# Verbinder_jr1.net
KiCad netlist of a schematic drawn in EAGLE
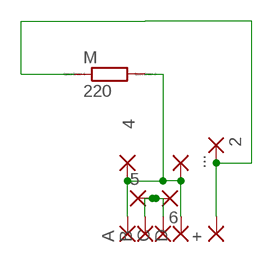
[diagram p0: schematic, sheet 1]

(export (version "E")
  (design (tool "Eeschema 10.0.6"))
  (components
    (comp (ref "+")
      (value "SMD2")
      (footprint "eagle-import:SMD1,27-2,54")
      (libsource (lib "eagle-import") (part "SMD2"))
    )
    (comp (ref "...")
      (value "SMD2")
      (footprint "eagle-import:SMD1,27-2,54")
      (libsource (lib "eagle-import") (part "SMD2"))
    )
    (comp (ref "2")
      (value "SMD2")
      (footprint "eagle-import:SMD1,27-2,54")
      (libsource (lib "eagle-import") (part "SMD2"))
    )
    (comp (ref "4")
      (value "SMD2")
      (footprint "eagle-import:SMD1,27-2,54")
      (libsource (lib "eagle-import") (part "SMD2"))
    )
    (comp (ref "5")
      (value "SMD2")
      (footprint "eagle-import:SMD1,27-2,54")
      (libsource (lib "eagle-import") (part "SMD2"))
    )
    (comp (ref "6")
      (value "SMD2")
      (footprint "eagle-import:SMD1,27-2,54")
      (libsource (lib "eagle-import") (part "SMD2"))
    )
    (comp (ref "A")
      (value "SMD2")
      (footprint "eagle-import:SMD1,27-2,54")
      (libsource (lib "eagle-import") (part "SMD2"))
    )
    (comp (ref "B")
      (value "SMD2")
      (footprint "eagle-import:SMD1,27-2,54")
      (libsource (lib "eagle-import") (part "SMD2"))
    )
    (comp (ref "C")
      (value "SMD2")
      (footprint "eagle-import:SMD1,27-2,54")
      (libsource (lib "eagle-import") (part "SMD2"))
    )
    (comp (ref "D")
      (value "SMD2")
      (footprint "eagle-import:SMD1,27-2,54")
      (libsource (lib "eagle-import") (part "SMD2"))
    )
    (comp (ref "M")
      (value "220")
      (footprint "eagle-import:0204_7")
      (libsource (lib "eagle-import") (part "R0204/7"))
    )
  )
  (nets
    (net (code "1") (name "Net-(+-P)") (class "Default")
      (node (ref "+") (pin "1") (pinfunction "P_1") (pintype "passive"))
      (node (ref "2") (pin "1") (pinfunction "P_1") (pintype "passive"))
      (node (ref "M") (pin "1") (pinfunction "1_1") (pintype "passive"))
    )
    (net (code "2") (name "Net-(...-P)") (class "Default")
      (node (ref "...") (pin "1") (pinfunction "P_1") (pintype "passive"))
      (node (ref "4") (pin "1") (pinfunction "P_1") (pintype "passive"))
      (node (ref "A") (pin "1") (pinfunction "P_1") (pintype "passive"))
      (node (ref "D") (pin "1") (pinfunction "P_1") (pintype "passive"))
      (node (ref "M") (pin "2") (pinfunction "2_2") (pintype "passive"))
    )
    (net (code "3") (name "Net-(5-P)") (class "Default")
      (node (ref "5") (pin "1") (pinfunction "P_1") (pintype "passive"))
      (node (ref "6") (pin "1") (pinfunction "P_1") (pintype "passive"))
      (node (ref "B") (pin "1") (pinfunction "P_1") (pintype "passive"))
      (node (ref "C") (pin "1") (pinfunction "P_1") (pintype "passive"))
    )
  )
)
